# tempature.net
KiCad netlist of a schematic drawn in Altium Designer
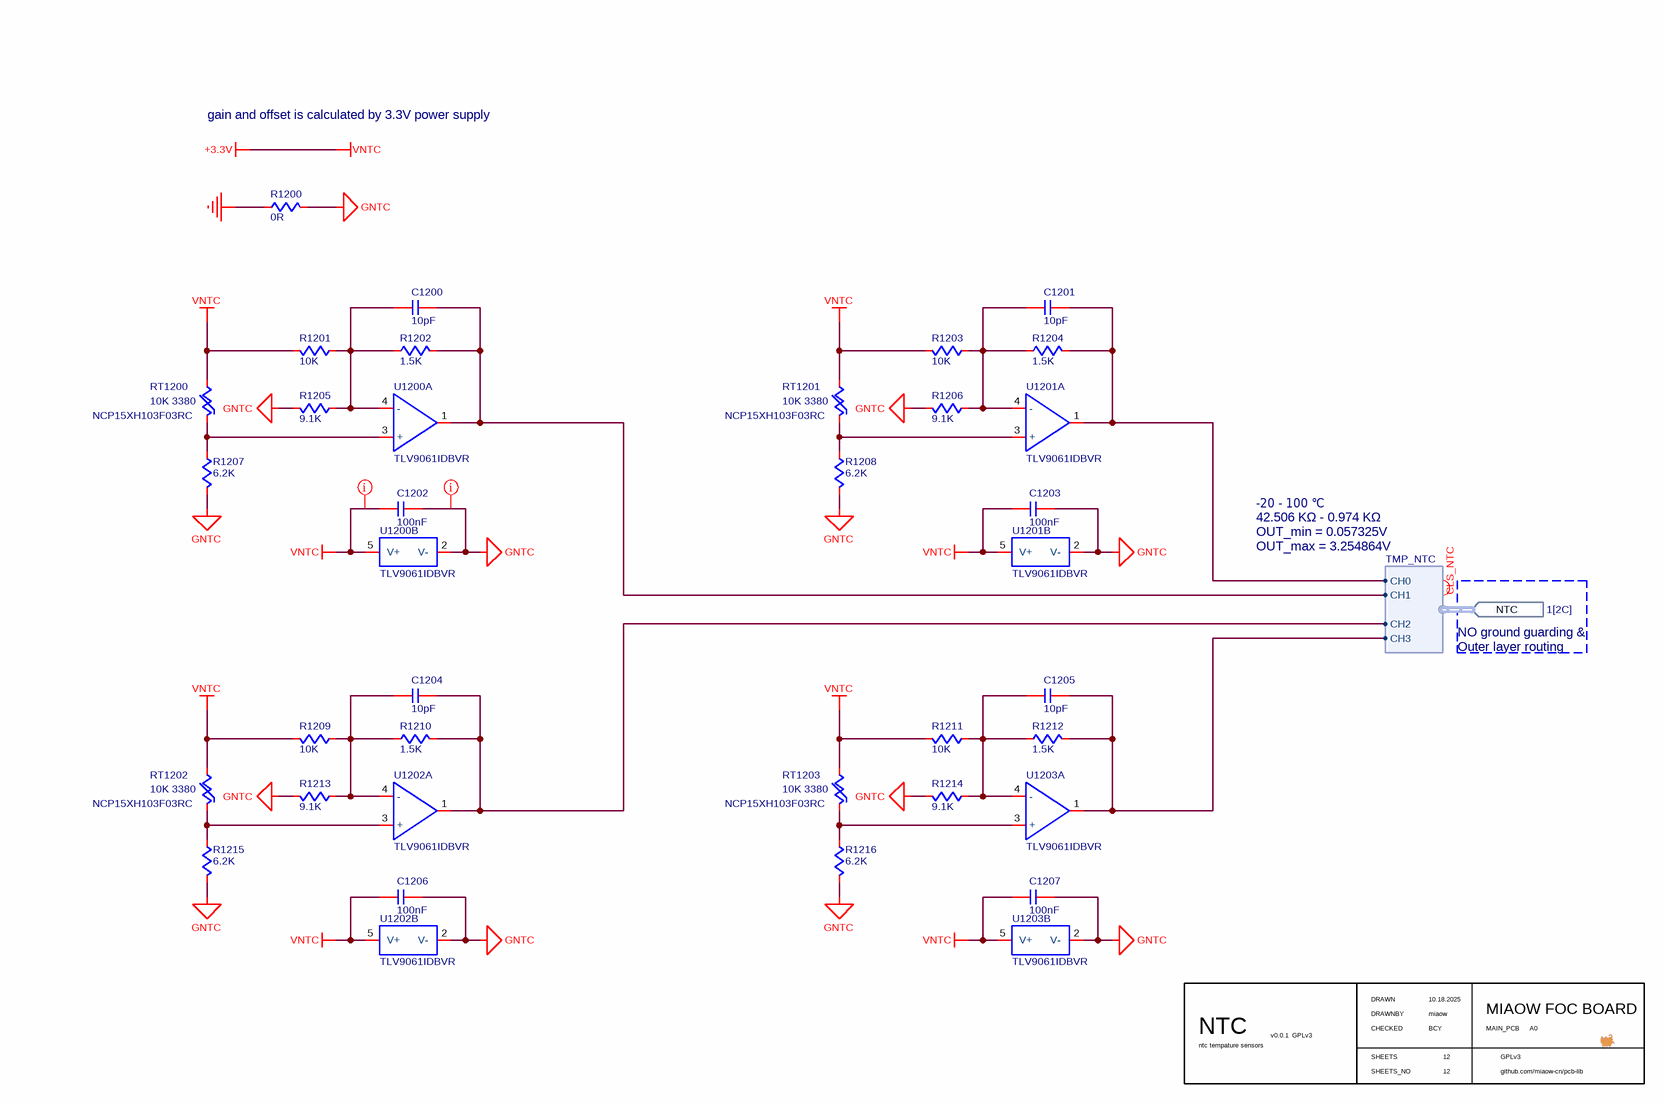
[diagram p0: tempature.SchDoc]

(export (version "E")
  (design (tool "Eeschema 10.0.6"))
  (components
    (comp (ref "C1200")
      (value "10pF")
      (footprint "mw:C0402")
      (fields (field (name "VOLTAGE") "25V") (field (name "Comment") "C-NOMO"))
      (libsource (lib "mw") (part "C-NOMO"))
    )
    (comp (ref "C1201")
      (value "10pF")
      (footprint "mw:C0402")
      (fields (field (name "VOLTAGE") "25V") (field (name "Comment") "C-NOMO"))
      (libsource (lib "mw") (part "C-NOMO"))
    )
    (comp (ref "C1202")
      (value "100nF")
      (footprint "mw:C0402")
      (fields (field (name "VOLTAGE") "25V") (field (name "Comment") "C-NOMO"))
      (libsource (lib "mw") (part "C-NOMO"))
    )
    (comp (ref "C1203")
      (value "100nF")
      (footprint "mw:C0402")
      (fields (field (name "VOLTAGE") "25V") (field (name "Comment") "C-NOMO"))
      (libsource (lib "mw") (part "C-NOMO"))
    )
    (comp (ref "C1204")
      (value "10pF")
      (footprint "mw:C0402")
      (fields (field (name "VOLTAGE") "25V") (field (name "Comment") "C-NOMO"))
      (libsource (lib "mw") (part "C-NOMO"))
    )
    (comp (ref "C1205")
      (value "10pF")
      (footprint "mw:C0402")
      (fields (field (name "VOLTAGE") "25V") (field (name "Comment") "C-NOMO"))
      (libsource (lib "mw") (part "C-NOMO"))
    )
    (comp (ref "C1206")
      (value "100nF")
      (footprint "mw:C0402")
      (fields (field (name "VOLTAGE") "25V") (field (name "Comment") "C-NOMO"))
      (libsource (lib "mw") (part "C-NOMO"))
    )
    (comp (ref "C1207")
      (value "100nF")
      (footprint "mw:C0402")
      (fields (field (name "VOLTAGE") "25V") (field (name "Comment") "C-NOMO"))
      (libsource (lib "mw") (part "C-NOMO"))
    )
    (comp (ref "R1200")
      (value "0R")
      (footprint "mw:R0402")
      (fields (field (name "Comment") "R"))
      (libsource (lib "mw") (part "R"))
    )
    (comp (ref "R1201")
      (value "10K")
      (footprint "mw:R0402")
      (fields (field (name "Comment") "R"))
      (libsource (lib "mw") (part "R"))
    )
    (comp (ref "R1202")
      (value "1.5K")
      (footprint "mw:R0402")
      (fields (field (name "Comment") "R"))
      (libsource (lib "mw") (part "R"))
    )
    (comp (ref "R1203")
      (value "10K")
      (footprint "mw:R0402")
      (fields (field (name "Comment") "R"))
      (libsource (lib "mw") (part "R"))
    )
    (comp (ref "R1204")
      (value "1.5K")
      (footprint "mw:R0402")
      (fields (field (name "Comment") "R"))
      (libsource (lib "mw") (part "R"))
    )
    (comp (ref "R1205")
      (value "9.1K")
      (footprint "mw:R0402")
      (fields (field (name "Comment") "R"))
      (libsource (lib "mw") (part "R"))
    )
    (comp (ref "R1206")
      (value "9.1K")
      (footprint "mw:R0402")
      (fields (field (name "Comment") "R"))
      (libsource (lib "mw") (part "R"))
    )
    (comp (ref "R1207")
      (value "6.2K")
      (footprint "mw:R0402")
      (fields (field (name "Comment") "R"))
      (libsource (lib "mw") (part "R"))
    )
    (comp (ref "R1208")
      (value "6.2K")
      (footprint "mw:R0402")
      (fields (field (name "Comment") "R"))
      (libsource (lib "mw") (part "R"))
    )
    (comp (ref "R1209")
      (value "10K")
      (footprint "mw:R0402")
      (fields (field (name "Comment") "R"))
      (libsource (lib "mw") (part "R"))
    )
    (comp (ref "R1210")
      (value "1.5K")
      (footprint "mw:R0402")
      (fields (field (name "Comment") "R"))
      (libsource (lib "mw") (part "R"))
    )
    (comp (ref "R1211")
      (value "10K")
      (footprint "mw:R0402")
      (fields (field (name "Comment") "R"))
      (libsource (lib "mw") (part "R"))
    )
    (comp (ref "R1212")
      (value "1.5K")
      (footprint "mw:R0402")
      (fields (field (name "Comment") "R"))
      (libsource (lib "mw") (part "R"))
    )
    (comp (ref "R1213")
      (value "9.1K")
      (footprint "mw:R0402")
      (fields (field (name "Comment") "R"))
      (libsource (lib "mw") (part "R"))
    )
    (comp (ref "R1214")
      (value "9.1K")
      (footprint "mw:R0402")
      (fields (field (name "Comment") "R"))
      (libsource (lib "mw") (part "R"))
    )
    (comp (ref "R1215")
      (value "6.2K")
      (footprint "mw:R0402")
      (fields (field (name "Comment") "R"))
      (libsource (lib "mw") (part "R"))
    )
    (comp (ref "R1216")
      (value "6.2K")
      (footprint "mw:R0402")
      (fields (field (name "Comment") "R"))
      (libsource (lib "mw") (part "R"))
    )
    (comp (ref "RT1200")
      (value "NCP15XH103F03RC")
      (footprint "mw:NTC0402")
      (description "NTC - 10K, 3380, 1%")
      (fields (field (name "ALTIUM_VALUE") "10K 3380"))
      (libsource (lib "mw") (part "NCP15XH103F03RC"))
    )
    (comp (ref "RT1201")
      (value "NCP15XH103F03RC")
      (footprint "mw:NTC0402")
      (description "NTC - 10K, 3380, 1%")
      (fields (field (name "ALTIUM_VALUE") "10K 3380"))
      (libsource (lib "mw") (part "NCP15XH103F03RC"))
    )
    (comp (ref "RT1202")
      (value "NCP15XH103F03RC")
      (footprint "mw:NTC0402")
      (description "NTC - 10K, 3380, 1%")
      (fields (field (name "ALTIUM_VALUE") "10K 3380"))
      (libsource (lib "mw") (part "NCP15XH103F03RC"))
    )
    (comp (ref "RT1203")
      (value "NCP15XH103F03RC")
      (footprint "mw:NTC0402")
      (description "NTC - 10K, 3380, 1%")
      (fields (field (name "ALTIUM_VALUE") "10K 3380"))
      (libsource (lib "mw") (part "NCP15XH103F03RC"))
    )
    (comp (ref "U1200")
      (value "TLV9061IDBVR")
      (footprint "mw:TLV9061IDBVR")
      (description "OPA - 1ch, 1.8V - 5.5V, r2r, 0.3mV, 10MHz, 10nVHz^0.5, 0.5pA")
      (libsource (lib "mw") (part "TLV9061IDBVR"))
    )
    (comp (ref "U1201")
      (value "TLV9061IDBVR")
      (footprint "mw:TLV9061IDBVR")
      (description "OPA - 1ch, 1.8V - 5.5V, r2r, 0.3mV, 10MHz, 10nVHz^0.5, 0.5pA")
      (libsource (lib "mw") (part "TLV9061IDBVR"))
    )
    (comp (ref "U1202")
      (value "TLV9061IDBVR")
      (footprint "mw:TLV9061IDBVR")
      (description "OPA - 1ch, 1.8V - 5.5V, r2r, 0.3mV, 10MHz, 10nVHz^0.5, 0.5pA")
      (libsource (lib "mw") (part "TLV9061IDBVR"))
    )
    (comp (ref "U1203")
      (value "TLV9061IDBVR")
      (footprint "mw:TLV9061IDBVR")
      (description "OPA - 1ch, 1.8V - 5.5V, r2r, 0.3mV, 10MHz, 10nVHz^0.5, 0.5pA")
      (libsource (lib "mw") (part "TLV9061IDBVR"))
    )
  )
  (nets
    (net (code "2") (name "+3.3V") (class "Default")
      (node (ref "C1202") (pin "2") (pinfunction "2_2") (pintype "passive"))
      (node (ref "C1203") (pin "2") (pinfunction "2_2") (pintype "passive"))
      (node (ref "C1206") (pin "2") (pinfunction "2_2") (pintype "passive"))
      (node (ref "C1207") (pin "2") (pinfunction "2_2") (pintype "passive"))
      (node (ref "R1201") (pin "1") (pinfunction "1_1") (pintype "passive"))
      (node (ref "R1203") (pin "1") (pinfunction "1_1") (pintype "passive"))
      (node (ref "R1209") (pin "1") (pinfunction "1_1") (pintype "passive"))
      (node (ref "R1211") (pin "1") (pinfunction "1_1") (pintype "passive"))
      (node (ref "RT1200") (pin "2") (pinfunction "2_2") (pintype "passive"))
      (node (ref "RT1201") (pin "2") (pinfunction "2_2") (pintype "passive"))
      (node (ref "RT1202") (pin "2") (pinfunction "2_2") (pintype "passive"))
      (node (ref "RT1203") (pin "2") (pinfunction "2_2") (pintype "passive"))
      (node (ref "U1200") (pin "5") (pinfunction "V+_5") (pintype "passive"))
      (node (ref "U1201") (pin "5") (pinfunction "V+_5") (pintype "passive"))
      (node (ref "U1202") (pin "5") (pinfunction "V+_5") (pintype "passive"))
      (node (ref "U1203") (pin "5") (pinfunction "V+_5") (pintype "passive"))
    )
    (net (code "4") (name "GND") (class "Default")
      (node (ref "R1200") (pin "2") (pinfunction "2_2") (pintype "passive"))
    )
    (net (code "5") (name "GNTC") (class "Default")
      (node (ref "C1202") (pin "1") (pinfunction "1_1") (pintype "passive"))
      (node (ref "C1203") (pin "1") (pinfunction "1_1") (pintype "passive"))
      (node (ref "C1206") (pin "1") (pinfunction "1_1") (pintype "passive"))
      (node (ref "C1207") (pin "1") (pinfunction "1_1") (pintype "passive"))
      (node (ref "R1200") (pin "1") (pinfunction "1_1") (pintype "passive"))
      (node (ref "R1205") (pin "1") (pinfunction "1_1") (pintype "passive"))
      (node (ref "R1206") (pin "1") (pinfunction "1_1") (pintype "passive"))
      (node (ref "R1207") (pin "1") (pinfunction "1_1") (pintype "passive"))
      (node (ref "R1208") (pin "1") (pinfunction "1_1") (pintype "passive"))
      (node (ref "R1213") (pin "1") (pinfunction "1_1") (pintype "passive"))
      (node (ref "R1214") (pin "1") (pinfunction "1_1") (pintype "passive"))
      (node (ref "R1215") (pin "1") (pinfunction "1_1") (pintype "passive"))
      (node (ref "R1216") (pin "1") (pinfunction "1_1") (pintype "passive"))
      (node (ref "U1200") (pin "2") (pinfunction "V-_2") (pintype "passive"))
      (node (ref "U1201") (pin "2") (pinfunction "V-_2") (pintype "passive"))
      (node (ref "U1202") (pin "2") (pinfunction "V-_2") (pintype "passive"))
      (node (ref "U1203") (pin "2") (pinfunction "V-_2") (pintype "passive"))
    )
    (net (code "6") (name "Net-(U1200A-+)") (class "Default")
      (node (ref "R1207") (pin "2") (pinfunction "2_2") (pintype "passive"))
      (node (ref "RT1200") (pin "1") (pinfunction "1_1") (pintype "passive"))
      (node (ref "U1200") (pin "3") (pinfunction "+_3") (pintype "passive"))
    )
    (net (code "7") (name "Net-(U1200A--)") (class "Default")
      (node (ref "C1200") (pin "2") (pinfunction "2_2") (pintype "passive"))
      (node (ref "R1201") (pin "2") (pinfunction "2_2") (pintype "passive"))
      (node (ref "R1202") (pin "2") (pinfunction "2_2") (pintype "passive"))
      (node (ref "R1205") (pin "2") (pinfunction "2_2") (pintype "passive"))
      (node (ref "U1200") (pin "4") (pinfunction "-_4") (pintype "passive"))
    )
    (net (code "8") (name "Net-(U1200A-OUT)") (class "Default")
      (node (ref "C1200") (pin "1") (pinfunction "1_1") (pintype "passive"))
      (node (ref "R1202") (pin "1") (pinfunction "1_1") (pintype "passive"))
      (node (ref "U1200") (pin "1") (pinfunction "OUT_1") (pintype "passive"))
    )
    (net (code "9") (name "Net-(U1201A-+)") (class "Default")
      (node (ref "R1208") (pin "2") (pinfunction "2_2") (pintype "passive"))
      (node (ref "RT1201") (pin "1") (pinfunction "1_1") (pintype "passive"))
      (node (ref "U1201") (pin "3") (pinfunction "+_3") (pintype "passive"))
    )
    (net (code "10") (name "Net-(U1201A--)") (class "Default")
      (node (ref "C1201") (pin "2") (pinfunction "2_2") (pintype "passive"))
      (node (ref "R1203") (pin "2") (pinfunction "2_2") (pintype "passive"))
      (node (ref "R1204") (pin "2") (pinfunction "2_2") (pintype "passive"))
      (node (ref "R1206") (pin "2") (pinfunction "2_2") (pintype "passive"))
      (node (ref "U1201") (pin "4") (pinfunction "-_4") (pintype "passive"))
    )
    (net (code "11") (name "Net-(U1201A-OUT)") (class "Default")
      (node (ref "C1201") (pin "1") (pinfunction "1_1") (pintype "passive"))
      (node (ref "R1204") (pin "1") (pinfunction "1_1") (pintype "passive"))
      (node (ref "U1201") (pin "1") (pinfunction "OUT_1") (pintype "passive"))
    )
    (net (code "12") (name "Net-(U1202A-+)") (class "Default")
      (node (ref "R1215") (pin "2") (pinfunction "2_2") (pintype "passive"))
      (node (ref "RT1202") (pin "1") (pinfunction "1_1") (pintype "passive"))
      (node (ref "U1202") (pin "3") (pinfunction "+_3") (pintype "passive"))
    )
    (net (code "13") (name "Net-(U1202A--)") (class "Default")
      (node (ref "C1204") (pin "2") (pinfunction "2_2") (pintype "passive"))
      (node (ref "R1209") (pin "2") (pinfunction "2_2") (pintype "passive"))
      (node (ref "R1210") (pin "2") (pinfunction "2_2") (pintype "passive"))
      (node (ref "R1213") (pin "2") (pinfunction "2_2") (pintype "passive"))
      (node (ref "U1202") (pin "4") (pinfunction "-_4") (pintype "passive"))
    )
    (net (code "14") (name "Net-(U1202A-OUT)") (class "Default")
      (node (ref "C1204") (pin "1") (pinfunction "1_1") (pintype "passive"))
      (node (ref "R1210") (pin "1") (pinfunction "1_1") (pintype "passive"))
      (node (ref "U1202") (pin "1") (pinfunction "OUT_1") (pintype "passive"))
    )
    (net (code "15") (name "Net-(U1203A-+)") (class "Default")
      (node (ref "R1216") (pin "2") (pinfunction "2_2") (pintype "passive"))
      (node (ref "RT1203") (pin "1") (pinfunction "1_1") (pintype "passive"))
      (node (ref "U1203") (pin "3") (pinfunction "+_3") (pintype "passive"))
    )
    (net (code "16") (name "Net-(U1203A--)") (class "Default")
      (node (ref "C1205") (pin "2") (pinfunction "2_2") (pintype "passive"))
      (node (ref "R1211") (pin "2") (pinfunction "2_2") (pintype "passive"))
      (node (ref "R1212") (pin "2") (pinfunction "2_2") (pintype "passive"))
      (node (ref "R1214") (pin "2") (pinfunction "2_2") (pintype "passive"))
      (node (ref "U1203") (pin "4") (pinfunction "-_4") (pintype "passive"))
    )
    (net (code "17") (name "Net-(U1203A-OUT)") (class "Default")
      (node (ref "C1205") (pin "1") (pinfunction "1_1") (pintype "passive"))
      (node (ref "R1212") (pin "1") (pinfunction "1_1") (pintype "passive"))
      (node (ref "U1203") (pin "1") (pinfunction "OUT_1") (pintype "passive"))
    )
  )
)
